# Daughter_Board_V3_1.net
KiCad netlist of a schematic drawn in EAGLE
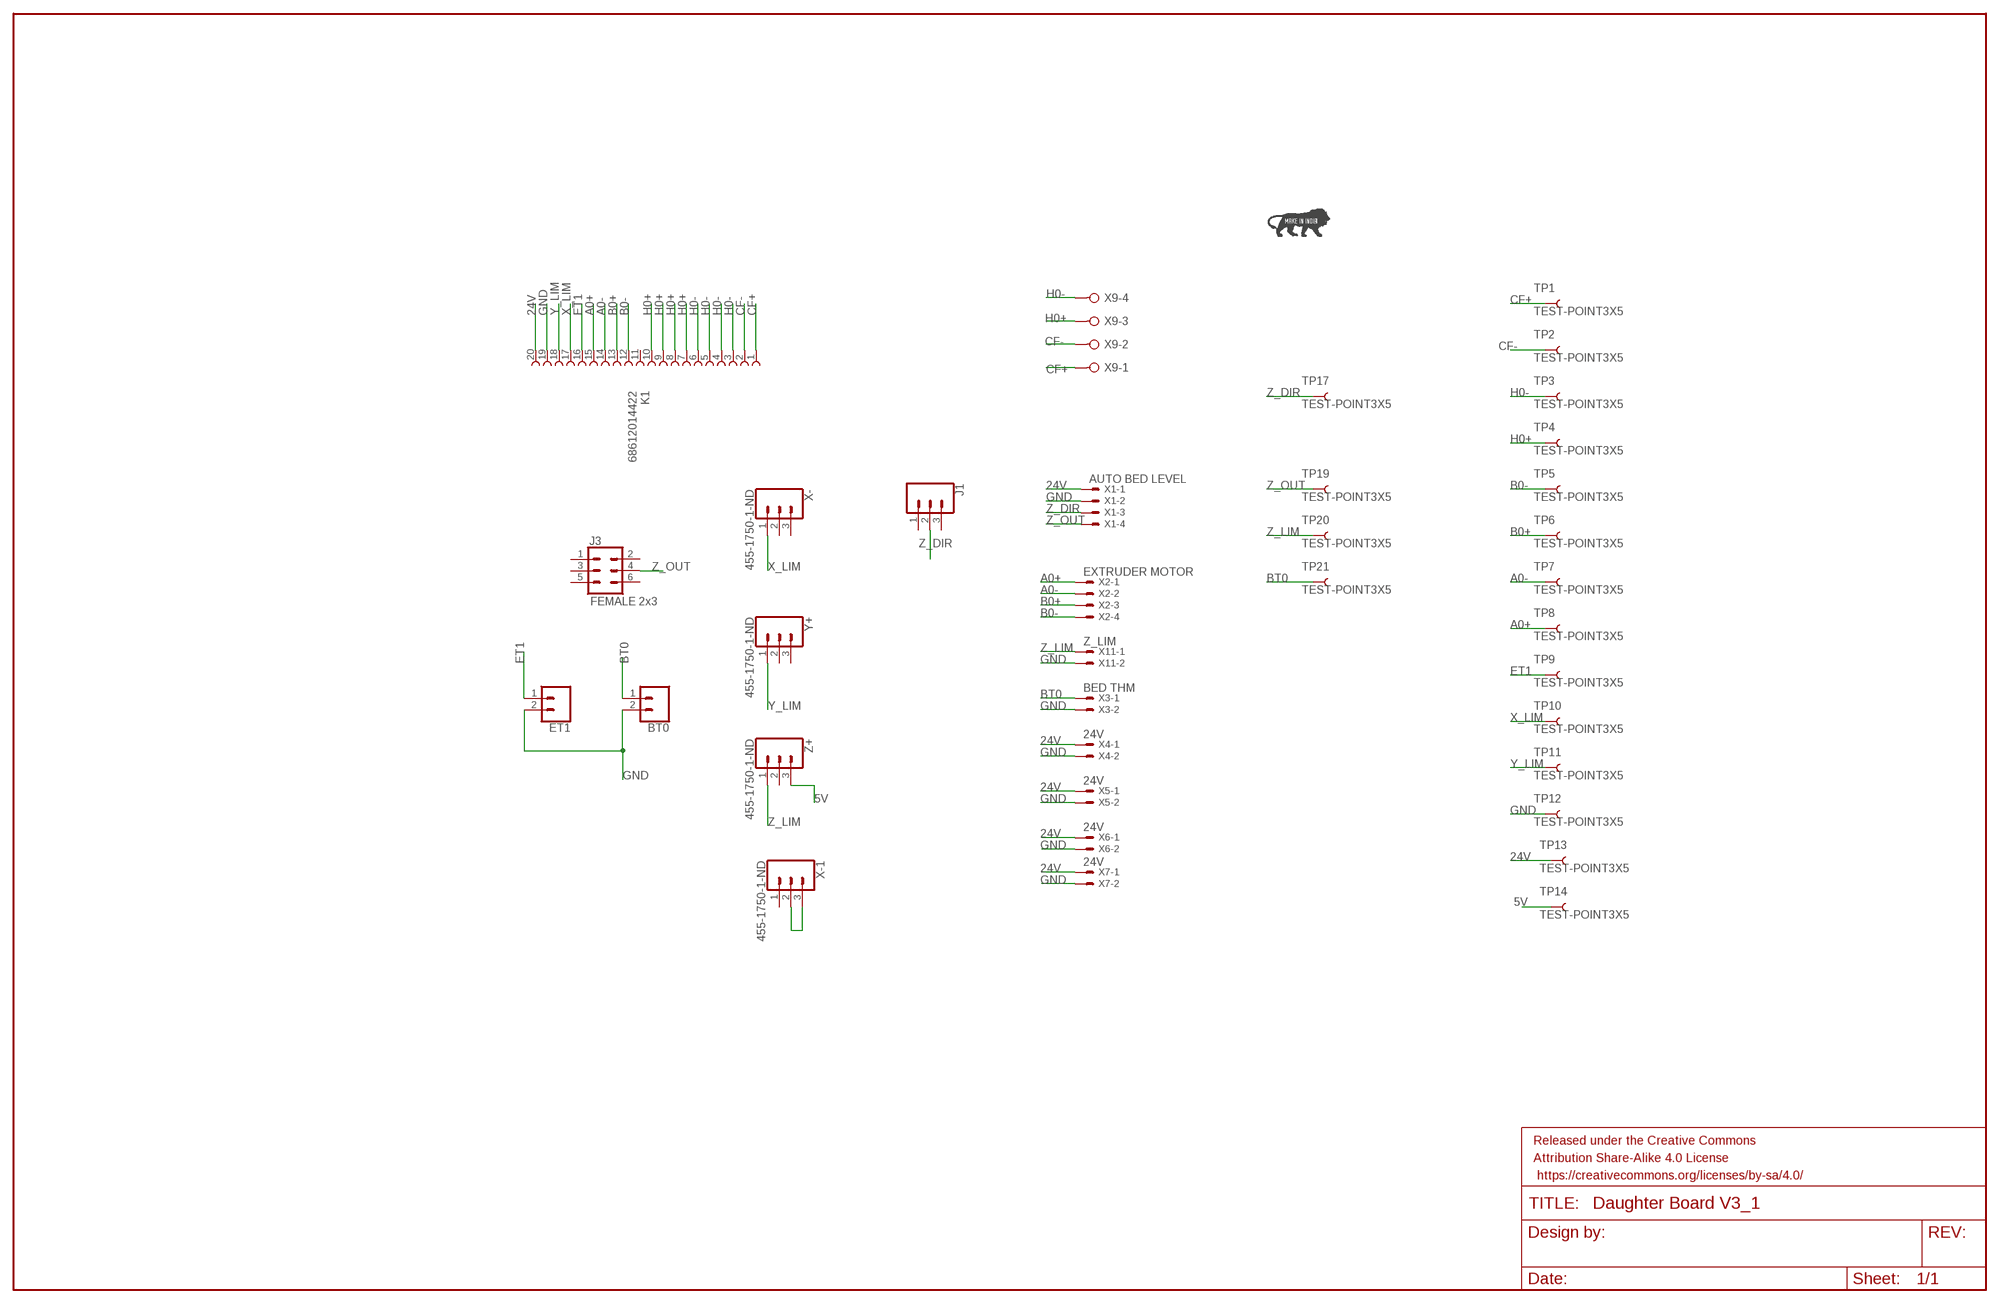
[diagram p0: schematic, sheet 1]

(export (version "E")
  (design (tool "Eeschema 10.0.6"))
  (components
    (comp (ref "BT0")
      (value "CONN_02")
      (footprint "eagle-import:1X02")
      (libsource (lib "eagle-import") (part "CONN_02"))
    )
    (comp (ref "ET1")
      (value "CONN_02")
      (footprint "eagle-import:1X02")
      (libsource (lib "eagle-import") (part "CONN_02"))
    )
    (comp (ref "FRAME1")
      (value "FRAME-LEDGER")
      (footprint "eagle-import:CREATIVE_COMMONS")
      (libsource (lib "eagle-import") (part "FRAME-LEDGER"))
    )
    (comp (ref "J1")
      (value "455-1750-1-ND")
      (footprint "eagle-import:1X03")
      (libsource (lib "eagle-import") (part "CONN_03"))
    )
    (comp (ref "J3")
      (value "FEMALE 2x3")
      (footprint "eagle-import:2X3")
      (libsource (lib "eagle-import") (part "CONN_03X2FEMALE"))
    )
    (comp (ref "K1")
      (value "68612014422")
      (footprint "eagle-import:68612014422")
      (libsource (lib "eagle-import") (part "68612014422"))
    )
    (comp (ref "TP1")
      (value "TEST-POINT3X5")
      (footprint "eagle-import:PAD.03X.05")
      (libsource (lib "eagle-import") (part "TEST-POINT3X5"))
    )
    (comp (ref "TP2")
      (value "TEST-POINT3X5")
      (footprint "eagle-import:PAD.03X.05")
      (libsource (lib "eagle-import") (part "TEST-POINT3X5"))
    )
    (comp (ref "TP3")
      (value "TEST-POINT3X5")
      (footprint "eagle-import:PAD.03X.05")
      (libsource (lib "eagle-import") (part "TEST-POINT3X5"))
    )
    (comp (ref "TP4")
      (value "TEST-POINT3X5")
      (footprint "eagle-import:PAD.03X.05")
      (libsource (lib "eagle-import") (part "TEST-POINT3X5"))
    )
    (comp (ref "TP5")
      (value "TEST-POINT3X5")
      (footprint "eagle-import:PAD.03X.05")
      (libsource (lib "eagle-import") (part "TEST-POINT3X5"))
    )
    (comp (ref "TP6")
      (value "TEST-POINT3X5")
      (footprint "eagle-import:PAD.03X.05")
      (libsource (lib "eagle-import") (part "TEST-POINT3X5"))
    )
    (comp (ref "TP7")
      (value "TEST-POINT3X5")
      (footprint "eagle-import:PAD.03X.05")
      (libsource (lib "eagle-import") (part "TEST-POINT3X5"))
    )
    (comp (ref "TP8")
      (value "TEST-POINT3X5")
      (footprint "eagle-import:PAD.03X.05")
      (libsource (lib "eagle-import") (part "TEST-POINT3X5"))
    )
    (comp (ref "TP9")
      (value "TEST-POINT3X5")
      (footprint "eagle-import:PAD.03X.05")
      (libsource (lib "eagle-import") (part "TEST-POINT3X5"))
    )
    (comp (ref "TP10")
      (value "TEST-POINT3X5")
      (footprint "eagle-import:PAD.03X.05")
      (libsource (lib "eagle-import") (part "TEST-POINT3X5"))
    )
    (comp (ref "TP11")
      (value "TEST-POINT3X5")
      (footprint "eagle-import:PAD.03X.05")
      (libsource (lib "eagle-import") (part "TEST-POINT3X5"))
    )
    (comp (ref "TP12")
      (value "TEST-POINT3X5")
      (footprint "eagle-import:PAD.03X.05")
      (libsource (lib "eagle-import") (part "TEST-POINT3X5"))
    )
    (comp (ref "TP13")
      (value "TEST-POINT3X5")
      (footprint "eagle-import:PAD.03X.05")
      (libsource (lib "eagle-import") (part "TEST-POINT3X5"))
    )
    (comp (ref "TP14")
      (value "TEST-POINT3X5")
      (footprint "eagle-import:PAD.03X.05")
      (libsource (lib "eagle-import") (part "TEST-POINT3X5"))
    )
    (comp (ref "TP17")
      (value "TEST-POINT3X5")
      (footprint "eagle-import:PAD.03X.05")
      (libsource (lib "eagle-import") (part "TEST-POINT3X5"))
    )
    (comp (ref "TP19")
      (value "TEST-POINT3X5")
      (footprint "eagle-import:PAD.03X.05")
      (libsource (lib "eagle-import") (part "TEST-POINT3X5"))
    )
    (comp (ref "TP20")
      (value "TEST-POINT3X5")
      (footprint "eagle-import:PAD.03X.05")
      (libsource (lib "eagle-import") (part "TEST-POINT3X5"))
    )
    (comp (ref "TP21")
      (value "TEST-POINT3X5")
      (footprint "eagle-import:PAD.03X.05")
      (libsource (lib "eagle-import") (part "TEST-POINT3X5"))
    )
    (comp (ref "U$2")
      (value "MAKEININDIA")
      (footprint "eagle-import:MAKEININDIA")
      (libsource (lib "eagle-import") (part "MAKEININDIA"))
    )
    (comp (ref "X-")
      (value "455-1750-1-ND")
      (footprint "eagle-import:1X03")
      (libsource (lib "eagle-import") (part "CONN_03"))
    )
    (comp (ref "X-1")
      (value "455-1750-1-ND")
      (footprint "eagle-import:1X03")
      (libsource (lib "eagle-import") (part "CONN_03"))
    )
    (comp (ref "X1")
      (value "AUTO BED LEVEL")
      (footprint "eagle-import:JST-XH-04-PACKAGE-LONG-PAD")
      (libsource (lib "eagle-import") (part "JST-XH-04-PIN-LONG-PAD"))
    )
    (comp (ref "X2")
      (value "EXTRUDER MOTOR")
      (footprint "eagle-import:JST-XH-04-PACKAGE-LONG-PAD")
      (libsource (lib "eagle-import") (part "JST-XH-04-PIN-LONG-PAD"))
    )
    (comp (ref "X3")
      (value "BED THM")
      (footprint "eagle-import:JST-XH-02-PACKAGE-LONG-PAD")
      (libsource (lib "eagle-import") (part "JST-XH-02-PIN-LONG-PAD"))
    )
    (comp (ref "X4")
      (value "24V")
      (footprint "eagle-import:JST-XH-02-PACKAGE-LONG-PAD")
      (libsource (lib "eagle-import") (part "JST-XH-02-PIN-LONG-PAD"))
    )
    (comp (ref "X5")
      (value "24V")
      (footprint "eagle-import:JST-XH-02-PACKAGE-LONG-PAD")
      (libsource (lib "eagle-import") (part "JST-XH-02-PIN-LONG-PAD"))
    )
    (comp (ref "X6")
      (value "24V")
      (footprint "eagle-import:JST-XH-02-PACKAGE-LONG-PAD")
      (libsource (lib "eagle-import") (part "JST-XH-02-PIN-LONG-PAD"))
    )
    (comp (ref "X7")
      (value "24V")
      (footprint "eagle-import:JST-XH-02-PACKAGE-LONG-PAD")
      (libsource (lib "eagle-import") (part "JST-XH-02-PIN-LONG-PAD"))
    )
    (comp (ref "X9")
      (value "W237-04P")
      (footprint "eagle-import:W237-4P")
      (libsource (lib "eagle-import") (part "W237-04P"))
    )
    (comp (ref "X11")
      (value "Z_LIM")
      (footprint "eagle-import:JST-XH-02-PACKAGE-LONG-PAD")
      (libsource (lib "eagle-import") (part "JST-XH-02-PIN-LONG-PAD"))
    )
    (comp (ref "Y+")
      (value "455-1750-1-ND")
      (footprint "eagle-import:1X03")
      (libsource (lib "eagle-import") (part "CONN_03"))
    )
    (comp (ref "Z+")
      (value "455-1750-1-ND")
      (footprint "eagle-import:1X03")
      (libsource (lib "eagle-import") (part "CONN_03"))
    )
  )
  (nets
    (net (code "1") (name "/5V") (class "Default")
      (node (ref "TP14") (pin "P$1") (pinfunction "1_P$1") (pintype "bidirectional"))
      (node (ref "Z+") (pin "3") (pinfunction "3_3") (pintype "passive"))
    )
    (net (code "2") (name "/24V") (class "Default")
      (node (ref "K1") (pin "20") (pinfunction "20_20") (pintype "passive"))
      (node (ref "TP13") (pin "P$1") (pinfunction "1_P$1") (pintype "bidirectional"))
      (node (ref "X1") (pin "1") (pinfunction "S_1") (pintype "passive"))
      (node (ref "X4") (pin "1") (pinfunction "S_1") (pintype "passive"))
      (node (ref "X5") (pin "1") (pinfunction "S_1") (pintype "passive"))
      (node (ref "X6") (pin "1") (pinfunction "S_1") (pintype "passive"))
      (node (ref "X7") (pin "1") (pinfunction "S_1") (pintype "passive"))
    )
    (net (code "3") (name "/A0+") (class "Default")
      (node (ref "K1") (pin "15") (pinfunction "15_15") (pintype "passive"))
      (node (ref "TP8") (pin "P$1") (pinfunction "1_P$1") (pintype "bidirectional"))
      (node (ref "X2") (pin "1") (pinfunction "S_1") (pintype "passive"))
    )
    (net (code "4") (name "/A0-") (class "Default")
      (node (ref "K1") (pin "14") (pinfunction "14_14") (pintype "passive"))
      (node (ref "TP7") (pin "P$1") (pinfunction "1_P$1") (pintype "bidirectional"))
      (node (ref "X2") (pin "2") (pinfunction "S_2") (pintype "passive"))
    )
    (net (code "5") (name "/B0+") (class "Default")
      (node (ref "K1") (pin "13") (pinfunction "13_13") (pintype "passive"))
      (node (ref "TP6") (pin "P$1") (pinfunction "1_P$1") (pintype "bidirectional"))
      (node (ref "X2") (pin "3") (pinfunction "S_3") (pintype "passive"))
    )
    (net (code "6") (name "/B0-") (class "Default")
      (node (ref "K1") (pin "12") (pinfunction "12_12") (pintype "passive"))
      (node (ref "TP5") (pin "P$1") (pinfunction "1_P$1") (pintype "bidirectional"))
      (node (ref "X2") (pin "4") (pinfunction "S_4") (pintype "passive"))
    )
    (net (code "7") (name "/BT0") (class "Default")
      (node (ref "BT0") (pin "1") (pinfunction "1_1") (pintype "passive"))
      (node (ref "TP21") (pin "P$1") (pinfunction "1_P$1") (pintype "bidirectional"))
      (node (ref "X3") (pin "1") (pinfunction "S_1") (pintype "passive"))
    )
    (net (code "8") (name "/CF+") (class "Default")
      (node (ref "K1") (pin "1") (pinfunction "1_1") (pintype "passive"))
      (node (ref "TP1") (pin "P$1") (pinfunction "1_P$1") (pintype "bidirectional"))
      (node (ref "X9") (pin "1") (pinfunction "KL_1") (pintype "passive"))
    )
    (net (code "9") (name "/CF-") (class "Default")
      (node (ref "K1") (pin "2") (pinfunction "2_2") (pintype "passive"))
      (node (ref "TP2") (pin "P$1") (pinfunction "1_P$1") (pintype "bidirectional"))
      (node (ref "X9") (pin "2") (pinfunction "KL_2") (pintype "passive"))
    )
    (net (code "10") (name "/ET1") (class "Default")
      (node (ref "ET1") (pin "1") (pinfunction "1_1") (pintype "passive"))
      (node (ref "K1") (pin "16") (pinfunction "16_16") (pintype "passive"))
      (node (ref "TP9") (pin "P$1") (pinfunction "1_P$1") (pintype "bidirectional"))
    )
    (net (code "11") (name "/GND") (class "Default")
      (node (ref "BT0") (pin "2") (pinfunction "2_2") (pintype "passive"))
      (node (ref "ET1") (pin "2") (pinfunction "2_2") (pintype "passive"))
      (node (ref "K1") (pin "19") (pinfunction "19_19") (pintype "passive"))
      (node (ref "TP12") (pin "P$1") (pinfunction "1_P$1") (pintype "bidirectional"))
      (node (ref "X1") (pin "2") (pinfunction "S_2") (pintype "passive"))
      (node (ref "X11") (pin "2") (pinfunction "S_2") (pintype "passive"))
      (node (ref "X3") (pin "2") (pinfunction "S_2") (pintype "passive"))
      (node (ref "X4") (pin "2") (pinfunction "S_2") (pintype "passive"))
      (node (ref "X5") (pin "2") (pinfunction "S_2") (pintype "passive"))
      (node (ref "X6") (pin "2") (pinfunction "S_2") (pintype "passive"))
      (node (ref "X7") (pin "2") (pinfunction "S_2") (pintype "passive"))
    )
    (net (code "12") (name "/H0+") (class "Default")
      (node (ref "K1") (pin "10") (pinfunction "10_10") (pintype "passive"))
      (node (ref "K1") (pin "7") (pinfunction "7_7") (pintype "passive"))
      (node (ref "K1") (pin "8") (pinfunction "8_8") (pintype "passive"))
      (node (ref "K1") (pin "9") (pinfunction "9_9") (pintype "passive"))
      (node (ref "TP4") (pin "P$1") (pinfunction "1_P$1") (pintype "bidirectional"))
      (node (ref "X9") (pin "3") (pinfunction "KL_3") (pintype "passive"))
    )
    (net (code "13") (name "/H0-") (class "Default")
      (node (ref "K1") (pin "3") (pinfunction "3_3") (pintype "passive"))
      (node (ref "K1") (pin "4") (pinfunction "4_4") (pintype "passive"))
      (node (ref "K1") (pin "5") (pinfunction "5_5") (pintype "passive"))
      (node (ref "K1") (pin "6") (pinfunction "6_6") (pintype "passive"))
      (node (ref "TP3") (pin "P$1") (pinfunction "1_P$1") (pintype "bidirectional"))
      (node (ref "X9") (pin "4") (pinfunction "KL_4") (pintype "passive"))
    )
    (net (code "14") (name "/X_LIM") (class "Default")
      (node (ref "K1") (pin "17") (pinfunction "17_17") (pintype "passive"))
      (node (ref "TP10") (pin "P$1") (pinfunction "1_P$1") (pintype "bidirectional"))
      (node (ref "X-") (pin "1") (pinfunction "1_1") (pintype "passive"))
    )
    (net (code "15") (name "/Y_LIM") (class "Default")
      (node (ref "K1") (pin "18") (pinfunction "18_18") (pintype "passive"))
      (node (ref "TP11") (pin "P$1") (pinfunction "1_P$1") (pintype "bidirectional"))
      (node (ref "Y+") (pin "1") (pinfunction "1_1") (pintype "passive"))
    )
    (net (code "16") (name "/Z_DIR") (class "Default")
      (node (ref "J1") (pin "2") (pinfunction "2_2") (pintype "passive"))
      (node (ref "TP17") (pin "P$1") (pinfunction "1_P$1") (pintype "bidirectional"))
      (node (ref "X1") (pin "3") (pinfunction "S_3") (pintype "passive"))
    )
    (net (code "17") (name "/Z_LIM") (class "Default")
      (node (ref "TP20") (pin "P$1") (pinfunction "1_P$1") (pintype "bidirectional"))
      (node (ref "X11") (pin "1") (pinfunction "S_1") (pintype "passive"))
      (node (ref "Z+") (pin "1") (pinfunction "1_1") (pintype "passive"))
    )
    (net (code "18") (name "/Z_OUT") (class "Default")
      (node (ref "J3") (pin "4") (pinfunction "4_4") (pintype "bidirectional"))
      (node (ref "TP19") (pin "P$1") (pinfunction "1_P$1") (pintype "bidirectional"))
      (node (ref "X1") (pin "4") (pinfunction "S_4") (pintype "passive"))
    )
    (net (code "19") (name "Net-(X-1-Pad2)") (class "Default")
      (node (ref "X-1") (pin "2") (pinfunction "2_2") (pintype "passive"))
      (node (ref "X-1") (pin "3") (pinfunction "3_3") (pintype "passive"))
    )
    (net (code "20") (name "unconnected-(J1-Pad1)") (class "Default")
      (node (ref "J1") (pin "1") (pinfunction "1_1") (pintype "passive"))
    )
    (net (code "21") (name "unconnected-(J1-Pad3)") (class "Default")
      (node (ref "J1") (pin "3") (pinfunction "3_3") (pintype "passive"))
    )
    (net (code "22") (name "unconnected-(J3-Pad1)") (class "Default")
      (node (ref "J3") (pin "1") (pinfunction "1_1") (pintype "bidirectional"))
    )
    (net (code "23") (name "unconnected-(J3-Pad2)") (class "Default")
      (node (ref "J3") (pin "2") (pinfunction "2_2") (pintype "bidirectional"))
    )
    (net (code "24") (name "unconnected-(J3-Pad3)") (class "Default")
      (node (ref "J3") (pin "3") (pinfunction "3_3") (pintype "bidirectional"))
    )
    (net (code "25") (name "unconnected-(J3-Pad5)") (class "Default")
      (node (ref "J3") (pin "5") (pinfunction "5_5") (pintype "bidirectional"))
    )
    (net (code "26") (name "unconnected-(J3-Pad6)") (class "Default")
      (node (ref "J3") (pin "6") (pinfunction "6_6") (pintype "bidirectional"))
    )
    (net (code "27") (name "unconnected-(K1-Pad11)") (class "Default")
      (node (ref "K1") (pin "11") (pinfunction "11_11") (pintype "passive"))
    )
    (net (code "28") (name "unconnected-(X--Pad2)") (class "Default")
      (node (ref "X-") (pin "2") (pinfunction "2_2") (pintype "passive"))
    )
    (net (code "29") (name "unconnected-(X--Pad3)") (class "Default")
      (node (ref "X-") (pin "3") (pinfunction "3_3") (pintype "passive"))
    )
    (net (code "30") (name "unconnected-(X-1-Pad1)") (class "Default")
      (node (ref "X-1") (pin "1") (pinfunction "1_1") (pintype "passive"))
    )
    (net (code "31") (name "unconnected-(Y+-Pad2)") (class "Default")
      (node (ref "Y+") (pin "2") (pinfunction "2_2") (pintype "passive"))
    )
    (net (code "32") (name "unconnected-(Y+-Pad3)") (class "Default")
      (node (ref "Y+") (pin "3") (pinfunction "3_3") (pintype "passive"))
    )
    (net (code "33") (name "unconnected-(Z+-Pad2)") (class "Default")
      (node (ref "Z+") (pin "2") (pinfunction "2_2") (pintype "passive"))
    )
  )
)
